# rf_conn.net
KiCad netlist of a schematic drawn in Altium Designer
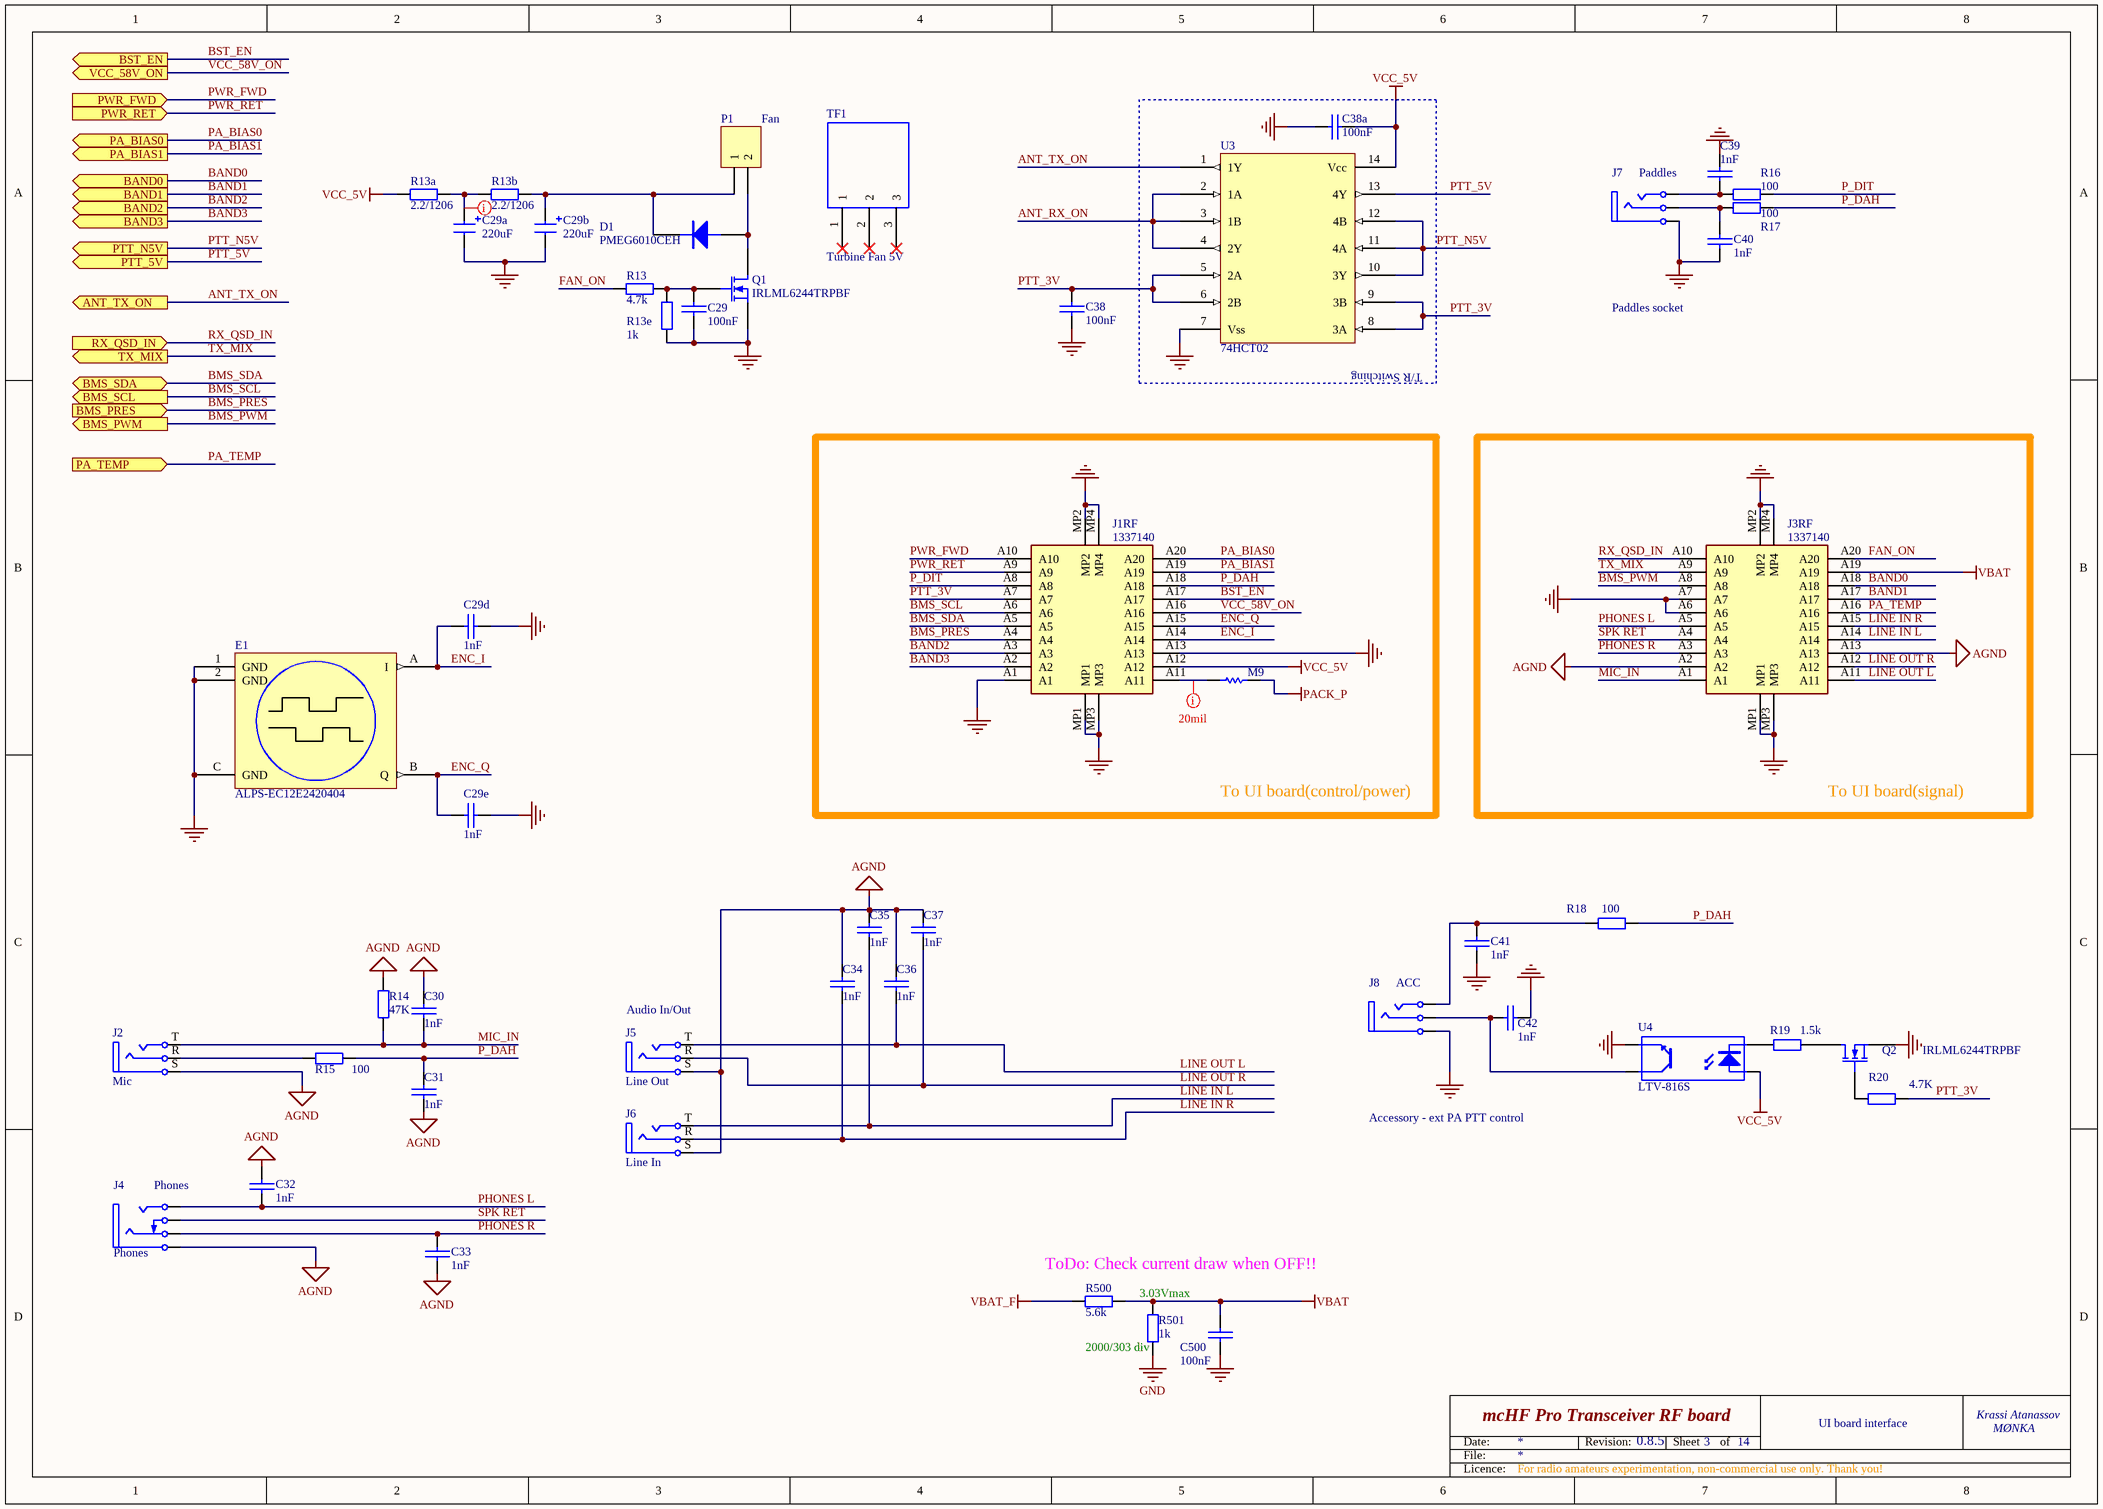
[diagram p0: rf_conn.SchDoc]

(export (version "E")
  (design (tool "Eeschema 10.0.6"))
  (components
    (comp (ref "C29")
      (value "100nF")
      (footprint "0805")
      (description "Capacitor")
      (libsource (lib "mcHF_ui") (part "CAP"))
    )
    (comp (ref "C29a")
      (value "220uF")
      (footprint "CAP_ALUM_Pro")
      (description "Electrolitic capacitor")
      (libsource (lib "mcHF_ui") (part "CAP-POL"))
    )
    (comp (ref "C29b")
      (value "220uF")
      (footprint "CAP_ALUM_Pro")
      (description "Electrolitic capacitor")
      (libsource (lib "mcHF_ui") (part "CAP-POL"))
    )
    (comp (ref "C29d")
      (value "1nF")
      (footprint "0805")
      (description "Capacitor")
      (libsource (lib "mcHF_ui") (part "CAP"))
    )
    (comp (ref "C29e")
      (value "1nF")
      (footprint "0805")
      (description "Capacitor")
      (libsource (lib "mcHF_ui") (part "CAP"))
    )
    (comp (ref "C30")
      (value "1nF")
      (footprint "0805")
      (description "Capacitor")
      (libsource (lib "mcHF_ui") (part "CAP"))
    )
    (comp (ref "C31")
      (value "1nF")
      (footprint "0805")
      (description "Capacitor")
      (libsource (lib "mcHF_ui") (part "CAP"))
    )
    (comp (ref "C32")
      (value "1nF")
      (footprint "0805")
      (description "Capacitor")
      (libsource (lib "mcHF_ui") (part "CAP"))
    )
    (comp (ref "C33")
      (value "1nF")
      (footprint "0805")
      (description "Capacitor")
      (libsource (lib "mcHF_ui") (part "CAP"))
    )
    (comp (ref "C34")
      (value "1nF")
      (footprint "0805")
      (description "Capacitor")
      (libsource (lib "mcHF_ui") (part "CAP"))
    )
    (comp (ref "C35")
      (value "1nF")
      (footprint "0805")
      (description "Capacitor")
      (libsource (lib "mcHF_ui") (part "CAP"))
    )
    (comp (ref "C36")
      (value "1nF")
      (footprint "0805")
      (description "Capacitor")
      (libsource (lib "mcHF_ui") (part "CAP"))
    )
    (comp (ref "C37")
      (value "1nF")
      (footprint "0805")
      (description "Capacitor")
      (libsource (lib "mcHF_ui") (part "CAP"))
    )
    (comp (ref "C38")
      (value "100nF")
      (footprint "0805")
      (description "Capacitor")
      (libsource (lib "mcHF_rf") (part "CAP"))
    )
    (comp (ref "C38a")
      (value "100nF")
      (footprint "0805")
      (description "Capacitor")
      (libsource (lib "mcHF_rf") (part "CAP"))
    )
    (comp (ref "C39")
      (value "1nF")
      (footprint "0805")
      (description "Capacitor")
      (libsource (lib "mcHF_rf") (part "CAP"))
    )
    (comp (ref "C40")
      (value "1nF")
      (footprint "0805")
      (description "Capacitor")
      (libsource (lib "mcHF_rf") (part "CAP"))
    )
    (comp (ref "C41")
      (value "1nF")
      (footprint "0805")
      (description "Capacitor")
      (libsource (lib "mcHF_rf") (part "CAP"))
    )
    (comp (ref "C42")
      (value "1nF")
      (footprint "0805")
      (description "Capacitor")
      (libsource (lib "mcHF_rf") (part "CAP"))
    )
    (comp (ref "C500")
      (value "100nF")
      (footprint "0805")
      (description "Capacitor")
      (libsource (lib "mcHF_rf") (part "CAP"))
    )
    (comp (ref "D1")
      (value "PMEG6010CEH")
      (footprint "SOD87")
      (description "DIODE, SCHOTTKY, 1A, 60V, SOD-123F")
      (libsource (lib "mcHF_rf") (part "PMEG6010CEH"))
    )
    (comp (ref "E1")
      (value "ALPS-EC12E2420404")
      (footprint "Encoder")
      (description "ALPS Rotary Encoder")
      (libsource (lib "__ui") (part "Encoder"))
    )
    (comp (ref "J1RF")
      (value "1337140")
      (footprint "1373866")
      (fields
        (field (name "MOUSER PART NUMBER") "651-1373866")
        (field (name "MANUFACTURER_PART_NUMBER") "1373866")
      )
      (libsource (lib "1373866") (part "1373866"))
    )
    (comp (ref "J2")
      (value "Mic")
      (footprint "MX-387GL_new1")
      (description "Jack Socket,Thru-Hole")
      (libsource (lib "mcHF_ui") (part "MX-387GL"))
    )
    (comp (ref "J3RF")
      (value "1337140")
      (footprint "1373866")
      (fields
        (field (name "MOUSER PART NUMBER") "651-1373866")
        (field (name "MANUFACTURER_PART_NUMBER") "1373866")
      )
      (libsource (lib "1373866") (part "1373866"))
    )
    (comp (ref "J4")
      (value "Phones")
      (footprint "KLBR4")
      (description "Jack Socket 4 pin")
      (fields (field (name "FUNCTION") "Phones"))
      (libsource (lib "mcHF_ui") (part "PhoneJack"))
    )
    (comp (ref "J5")
      (value "Line Out")
      (footprint "MX-387GL_new1")
      (description "Jack Socket,Thru-Hole")
      (libsource (lib "mcHF_ui") (part "MX-387GL"))
    )
    (comp (ref "J6")
      (value "Line In")
      (footprint "MX-387GL_new1")
      (description "Jack Socket,Thru-Hole")
      (libsource (lib "mcHF_ui") (part "MX-387GL"))
    )
    (comp (ref "J7")
      (value "Paddles")
      (footprint "MX-387GL_new1")
      (description "Jack Socket,Thru-Hole")
      (libsource (lib "mcHF_rf") (part "Phonejack3"))
    )
    (comp (ref "J8")
      (value "ACC")
      (footprint "MX-387GL_new1")
      (description "Jack Socket,Thru-Hole")
      (libsource (lib "mcHF_rf") (part "Phonejack3"))
    )
    (comp (ref "M9")
      (value "0")
      (footprint "SB_0603_10")
      (description "Link")
      (fields (field (name "PUBLISHER") "Altium Limited"))
      (libsource (lib "__ui") (part "Link"))
    )
    (comp (ref "P1")
      (value "Fan")
      (footprint "MHDR1X2_m")
      (description "Header, 2-Pin")
      (fields (field (name "PUBLISHER") "Altium Limited"))
      (libsource (lib "Miscellaneous Connectors") (part "MHDR1X2"))
    )
    (comp (ref "Q1")
      (value "IRLML6244TRPBF")
      (footprint "SOT-23-Pro")
      (description "N-Channel MOSFET")
      (libsource (lib "mcHF_ui_b") (part "MOSFET-N"))
    )
    (comp (ref "Q2")
      (value "IRLML6244TRPBF")
      (footprint "SOT-23-Pro")
      (description "N-Channel MOSFET")
      (libsource (lib "mcHF_ui_b") (part "MOSFET-N"))
    )
    (comp (ref "R13")
      (value "4.7k")
      (footprint "0805")
      (description "Resistor")
      (libsource (lib "") (part "RES_3"))
    )
    (comp (ref "R13a")
      (value "2.2/1206")
      (footprint "1206")
      (description "Resistor")
      (libsource (lib "") (part "RES_2"))
    )
    (comp (ref "R13b")
      (value "2.2/1206")
      (footprint "1206")
      (description "Resistor")
      (libsource (lib "") (part "RES_2"))
    )
    (comp (ref "R13e")
      (value "1k")
      (footprint "0805")
      (description "Resistor")
      (libsource (lib "") (part "RES_1"))
    )
    (comp (ref "R14")
      (value "47K")
      (footprint "0805")
      (description "Resistor")
      (libsource (lib "mcHF_ui") (part "RES"))
    )
    (comp (ref "R15")
      (value "100")
      (footprint "0805")
      (description "Resistor")
      (libsource (lib "") (part "RES_2"))
    )
    (comp (ref "R16")
      (value "100")
      (footprint "0805")
      (description "Resistor")
      (libsource (lib "*") (part "RES"))
    )
    (comp (ref "R17")
      (value "100")
      (footprint "0805")
      (description "Resistor")
      (libsource (lib "*") (part "RES"))
    )
    (comp (ref "R18")
      (value "100")
      (footprint "0805")
      (description "Resistor")
      (libsource (lib "*") (part "RES"))
    )
    (comp (ref "R19")
      (value "1.5k")
      (footprint "0805")
      (description "Resistor")
      (libsource (lib "mcHF_rf") (part "RES"))
    )
    (comp (ref "R20")
      (value "4.7K")
      (footprint "0805")
      (description "Resistor")
      (libsource (lib "mcHF_rf") (part "RES"))
    )
    (comp (ref "R500")
      (value "5.6k")
      (footprint "0805")
      (description "Resistor")
      (libsource (lib "mcHF_rf") (part "RES"))
    )
    (comp (ref "R501")
      (value "1k")
      (footprint "0805")
      (description "Resistor")
      (libsource (lib "") (part "RES_1"))
    )
    (comp (ref "TF1")
      (value "Turbine Fan 5V")
      (footprint "TFAN")
      (description "5V Turbine Fan, 40x40mm")
      (libsource (lib "__rf") (part "FAN5V"))
    )
    (comp (ref "U3")
      (value "74HCT02")
      (footprint "SO-14")
      (description "Quad 2-input NOR gate")
      (libsource (lib "mcHF_rf") (part "74HCT02"))
    )
    (comp (ref "U4")
      (value "LTV-816S")
      (footprint "SMDIP-4_new1")
      (description "OPTOCOUPLER, SMDIP-4, TR O/P")
      (libsource (lib "mcHF_rf") (part "ISP817XSM"))
    )
  )
  (nets
    (net (code "1") (name "/ANT_RX_ON") (class "Default")
      (node (ref "U3") (pin "2") (pinfunction "1A_2") (pintype "input"))
      (node (ref "U3") (pin "3") (pinfunction "1B_3") (pintype "input"))
      (node (ref "U3") (pin "4") (pinfunction "2Y_4") (pintype "output"))
    )
    (net (code "2") (name "/ANT_TX_ON") (class "Default")
      (node (ref "U3") (pin "1") (pinfunction "1Y_1") (pintype "output"))
    )
    (net (code "3") (name "/BAND0") (class "Default")
      (node (ref "J3RF") (pin "A18") (pinfunction "A18_A18") (pintype "passive"))
    )
    (net (code "4") (name "/BAND1") (class "Default")
      (node (ref "J3RF") (pin "A17") (pinfunction "A17_A17") (pintype "passive"))
    )
    (net (code "5") (name "/BAND2") (class "Default")
      (node (ref "J1RF") (pin "A3") (pinfunction "A3_A3") (pintype "passive"))
    )
    (net (code "6") (name "/BAND3") (class "Default")
      (node (ref "J1RF") (pin "A2") (pinfunction "A2_A2") (pintype "passive"))
    )
    (net (code "7") (name "/BMS_PRES") (class "Default")
      (node (ref "J1RF") (pin "A4") (pinfunction "A4_A4") (pintype "passive"))
    )
    (net (code "8") (name "/BMS_PWM") (class "Default")
      (node (ref "J3RF") (pin "A8") (pinfunction "A8_A8") (pintype "passive"))
    )
    (net (code "9") (name "/BMS_SCL") (class "Default")
      (node (ref "J1RF") (pin "A6") (pinfunction "A6_A6") (pintype "passive"))
    )
    (net (code "10") (name "/BMS_SDA") (class "Default")
      (node (ref "J1RF") (pin "A5") (pinfunction "A5_A5") (pintype "passive"))
    )
    (net (code "11") (name "/BST_EN") (class "Default")
      (node (ref "J1RF") (pin "A17") (pinfunction "A17_A17") (pintype "passive"))
    )
    (net (code "12") (name "/ENC_I") (class "Default")
      (node (ref "C29d") (pin "1") (pinfunction "1_1") (pintype "passive"))
      (node (ref "E1") (pin "A") (pinfunction "I_A") (pintype "output"))
      (node (ref "J1RF") (pin "A14") (pinfunction "A14_A14") (pintype "passive"))
    )
    (net (code "13") (name "/ENC_Q") (class "Default")
      (node (ref "C29e") (pin "1") (pinfunction "1_1") (pintype "passive"))
      (node (ref "E1") (pin "B") (pinfunction "Q_B") (pintype "output"))
      (node (ref "J1RF") (pin "A15") (pinfunction "A15_A15") (pintype "passive"))
    )
    (net (code "14") (name "/FAN_ON") (class "Default")
      (node (ref "J3RF") (pin "A20") (pinfunction "A20_A20") (pintype "passive"))
      (node (ref "R13") (pin "2") (pinfunction "2_2") (pintype "passive"))
    )
    (net (code "15") (name "/LINE IN L") (class "Default")
      (node (ref "C35") (pin "2") (pinfunction "2_2") (pintype "passive"))
      (node (ref "J3RF") (pin "A14") (pinfunction "A14_A14") (pintype "passive"))
      (node (ref "J6") (pin "T") (pinfunction "1_T") (pintype "passive"))
    )
    (net (code "16") (name "/LINE IN R") (class "Default")
      (node (ref "C34") (pin "2") (pinfunction "2_2") (pintype "passive"))
      (node (ref "J3RF") (pin "A15") (pinfunction "A15_A15") (pintype "passive"))
      (node (ref "J6") (pin "R") (pinfunction "3_R") (pintype "passive"))
    )
    (net (code "17") (name "/LINE OUT L") (class "Default")
      (node (ref "C36") (pin "2") (pinfunction "2_2") (pintype "passive"))
      (node (ref "J3RF") (pin "A11") (pinfunction "A11_A11") (pintype "passive"))
      (node (ref "J5") (pin "T") (pinfunction "1_T") (pintype "passive"))
    )
    (net (code "18") (name "/LINE OUT R") (class "Default")
      (node (ref "C37") (pin "2") (pinfunction "2_2") (pintype "passive"))
      (node (ref "J3RF") (pin "A12") (pinfunction "A12_A12") (pintype "passive"))
      (node (ref "J5") (pin "R") (pinfunction "3_R") (pintype "passive"))
    )
    (net (code "19") (name "/MIC_IN") (class "Default")
      (node (ref "C30") (pin "2") (pinfunction "2_2") (pintype "passive"))
      (node (ref "J2") (pin "T") (pinfunction "1_T") (pintype "passive"))
      (node (ref "J3RF") (pin "A1") (pinfunction "A1_A1") (pintype "passive"))
      (node (ref "R14") (pin "1") (pinfunction "1_1") (pintype "passive"))
    )
    (net (code "20") (name "/PA_BIAS0") (class "Default")
      (node (ref "J1RF") (pin "A20") (pinfunction "A20_A20") (pintype "passive"))
    )
    (net (code "21") (name "/PA_BIAS1") (class "Default")
      (node (ref "J1RF") (pin "A19") (pinfunction "A19_A19") (pintype "passive"))
    )
    (net (code "22") (name "/PA_TEMP") (class "Default")
      (node (ref "J3RF") (pin "A16") (pinfunction "A16_A16") (pintype "passive"))
    )
    (net (code "23") (name "/PHONES L") (class "Default")
      (node (ref "C32") (pin "1") (pinfunction "1_1") (pintype "passive"))
      (node (ref "J3RF") (pin "A5") (pinfunction "A5_A5") (pintype "passive"))
      (node (ref "J4") (pin "T") (pinfunction "T_T") (pintype "passive"))
    )
    (net (code "24") (name "/PHONES R") (class "Default")
      (node (ref "C33") (pin "2") (pinfunction "2_2") (pintype "passive"))
      (node (ref "J3RF") (pin "A3") (pinfunction "A3_A3") (pintype "passive"))
      (node (ref "J4") (pin "R") (pinfunction "R_R") (pintype "passive"))
    )
    (net (code "25") (name "/PTT_3V") (class "Default")
      (node (ref "C38") (pin "1") (pinfunction "1_1") (pintype "passive"))
      (node (ref "J1RF") (pin "A7") (pinfunction "A7_A7") (pintype "passive"))
      (node (ref "R20") (pin "2") (pinfunction "2_2") (pintype "passive"))
      (node (ref "U3") (pin "5") (pinfunction "2A_5") (pintype "input"))
      (node (ref "U3") (pin "6") (pinfunction "2B_6") (pintype "input"))
      (node (ref "U3") (pin "8") (pinfunction "3A_8") (pintype "input"))
      (node (ref "U3") (pin "9") (pinfunction "3B_9") (pintype "input"))
    )
    (net (code "26") (name "/PTT_5V") (class "Default")
      (node (ref "U3") (pin "13") (pinfunction "4Y_13") (pintype "output"))
    )
    (net (code "27") (name "/PTT_N5V") (class "Default")
      (node (ref "U3") (pin "10") (pinfunction "3Y_10") (pintype "output"))
      (node (ref "U3") (pin "11") (pinfunction "4A_11") (pintype "input"))
      (node (ref "U3") (pin "12") (pinfunction "4B_12") (pintype "input"))
    )
    (net (code "28") (name "/PWR_FWD") (class "Default")
      (node (ref "J1RF") (pin "A10") (pinfunction "A10_A10") (pintype "passive"))
    )
    (net (code "29") (name "/PWR_RET") (class "Default")
      (node (ref "J1RF") (pin "A9") (pinfunction "A9_A9") (pintype "passive"))
    )
    (net (code "30") (name "/P_DAH") (class "Default")
      (node (ref "C31") (pin "1") (pinfunction "1_1") (pintype "passive"))
      (node (ref "J1RF") (pin "A18") (pinfunction "A18_A18") (pintype "passive"))
      (node (ref "R15") (pin "2") (pinfunction "2_2") (pintype "passive"))
      (node (ref "R17") (pin "1") (pinfunction "1_1") (pintype "passive"))
      (node (ref "R18") (pin "1") (pinfunction "1_1") (pintype "passive"))
    )
    (net (code "31") (name "/P_DIT") (class "Default")
      (node (ref "J1RF") (pin "A8") (pinfunction "A8_A8") (pintype "passive"))
      (node (ref "R16") (pin "1") (pinfunction "1_1") (pintype "passive"))
    )
    (net (code "32") (name "/RX_QSD_IN") (class "Default")
      (node (ref "J3RF") (pin "A10") (pinfunction "A10_A10") (pintype "passive"))
    )
    (net (code "33") (name "/SPK RET") (class "Default")
      (node (ref "J3RF") (pin "A4") (pinfunction "A4_A4") (pintype "passive"))
      (node (ref "J4") (pin "B") (pinfunction "B_B") (pintype "passive"))
    )
    (net (code "34") (name "/TX_MIX") (class "Default")
      (node (ref "J3RF") (pin "A9") (pinfunction "A9_A9") (pintype "passive"))
    )
    (net (code "35") (name "/VCC_58V_ON") (class "Default")
      (node (ref "J1RF") (pin "A16") (pinfunction "A16_A16") (pintype "passive"))
    )
    (net (code "36") (name "AGND") (class "Default")
      (node (ref "C30") (pin "1") (pinfunction "1_1") (pintype "passive"))
      (node (ref "C31") (pin "2") (pinfunction "2_2") (pintype "passive"))
      (node (ref "C32") (pin "2") (pinfunction "2_2") (pintype "passive"))
      (node (ref "C33") (pin "1") (pinfunction "1_1") (pintype "passive"))
      (node (ref "C34") (pin "1") (pinfunction "1_1") (pintype "passive"))
      (node (ref "C35") (pin "1") (pinfunction "1_1") (pintype "passive"))
      (node (ref "C36") (pin "1") (pinfunction "1_1") (pintype "passive"))
      (node (ref "C37") (pin "1") (pinfunction "1_1") (pintype "passive"))
      (node (ref "J2") (pin "S") (pinfunction "2_S") (pintype "power_in"))
      (node (ref "J3RF") (pin "A13") (pinfunction "A13_A13") (pintype "passive"))
      (node (ref "J3RF") (pin "A2") (pinfunction "A2_A2") (pintype "passive"))
      (node (ref "J4") (pin "S") (pinfunction "S_S") (pintype "power_in"))
      (node (ref "J5") (pin "S") (pinfunction "2_S") (pintype "power_in"))
      (node (ref "J6") (pin "S") (pinfunction "2_S") (pintype "power_in"))
      (node (ref "R14") (pin "2") (pinfunction "2_2") (pintype "passive"))
    )
    (net (code "37") (name "GND") (class "Default")
      (node (ref "C29") (pin "2") (pinfunction "2_2") (pintype "passive"))
      (node (ref "C29a") (pin "2") (pinfunction "2_2") (pintype "passive"))
      (node (ref "C29b") (pin "2") (pinfunction "2_2") (pintype "passive"))
      (node (ref "C29d") (pin "2") (pinfunction "2_2") (pintype "passive"))
      (node (ref "C29e") (pin "2") (pinfunction "2_2") (pintype "passive"))
      (node (ref "C38") (pin "2") (pinfunction "2_2") (pintype "passive"))
      (node (ref "C38a") (pin "2") (pinfunction "2_2") (pintype "passive"))
      (node (ref "C39") (pin "2") (pinfunction "2_2") (pintype "passive"))
      (node (ref "C40") (pin "1") (pinfunction "1_1") (pintype "passive"))
      (node (ref "C41") (pin "2") (pinfunction "2_2") (pintype "passive"))
      (node (ref "C42") (pin "1") (pinfunction "1_1") (pintype "passive"))
      (node (ref "C500") (pin "2") (pinfunction "2_2") (pintype "passive"))
      (node (ref "E1") (pin "1") (pinfunction "GND_1") (pintype "power_in"))
      (node (ref "E1") (pin "2") (pinfunction "GND_2") (pintype "power_in"))
      (node (ref "E1") (pin "C") (pinfunction "GND_C") (pintype "power_in"))
      (node (ref "J1RF") (pin "A1") (pinfunction "A1_A1") (pintype "passive"))
      (node (ref "J1RF") (pin "A13") (pinfunction "A13_A13") (pintype "passive"))
      (node (ref "J1RF") (pin "MP1") (pinfunction "MP1_MP1") (pintype "passive"))
      (node (ref "J1RF") (pin "MP2") (pinfunction "MP2_MP2") (pintype "passive"))
      (node (ref "J1RF") (pin "MP3") (pinfunction "MP3_MP3") (pintype "passive"))
      (node (ref "J1RF") (pin "MP4") (pinfunction "MP4_MP4") (pintype "passive"))
      (node (ref "J3RF") (pin "A6") (pinfunction "A6_A6") (pintype "passive"))
      (node (ref "J3RF") (pin "A7") (pinfunction "A7_A7") (pintype "passive"))
      (node (ref "J3RF") (pin "MP1") (pinfunction "MP1_MP1") (pintype "passive"))
      (node (ref "J3RF") (pin "MP2") (pinfunction "MP2_MP2") (pintype "passive"))
      (node (ref "J3RF") (pin "MP3") (pinfunction "MP3_MP3") (pintype "passive"))
      (node (ref "J3RF") (pin "MP4") (pinfunction "MP4_MP4") (pintype "passive"))
      (node (ref "J7") (pin "S") (pinfunction "S_S") (pintype "power_in"))
      (node (ref "J8") (pin "S") (pinfunction "S_S") (pintype "power_in"))
      (node (ref "Q1") (pin "2") (pinfunction "S_2") (pintype "passive"))
      (node (ref "Q2") (pin "2") (pinfunction "S_2") (pintype "passive"))
      (node (ref "R13e") (pin "2") (pinfunction "2_2") (pintype "passive"))
      (node (ref "R501") (pin "2") (pinfunction "2_2") (pintype "passive"))
      (node (ref "U3") (pin "7") (pinfunction "Vss_7") (pintype "power_in"))
      (node (ref "U4") (pin "3") (pinfunction "E_3") (pintype "passive"))
    )
    (net (code "38") (name "Net-(C29a-Pad1)") (class "Default")
      (node (ref "C29a") (pin "1") (pinfunction "1_1") (pintype "passive"))
      (node (ref "R13a") (pin "2") (pinfunction "2_2") (pintype "passive"))
      (node (ref "R13b") (pin "1") (pinfunction "1_1") (pintype "passive"))
    )
    (net (code "39") (name "Net-(C39-Pad1)") (class "Default")
      (node (ref "C39") (pin "1") (pinfunction "1_1") (pintype "passive"))
      (node (ref "J7") (pin "T") (pinfunction "T_T") (pintype "passive"))
      (node (ref "R16") (pin "2") (pinfunction "2_2") (pintype "passive"))
    )
    (net (code "40") (name "Net-(C40-Pad2)") (class "Default")
      (node (ref "C40") (pin "2") (pinfunction "2_2") (pintype "passive"))
      (node (ref "J7") (pin "R") (pinfunction "R_R") (pintype "passive"))
      (node (ref "R17") (pin "2") (pinfunction "2_2") (pintype "passive"))
    )
    (net (code "41") (name "Net-(C41-Pad1)") (class "Default")
      (node (ref "C41") (pin "1") (pinfunction "1_1") (pintype "passive"))
      (node (ref "J8") (pin "T") (pinfunction "T_T") (pintype "passive"))
      (node (ref "R18") (pin "2") (pinfunction "2_2") (pintype "passive"))
    )
    (net (code "42") (name "Net-(D1-A)") (class "Default")
      (node (ref "D1") (pin "1") (pinfunction "A_1") (pintype "passive"))
      (node (ref "P1") (pin "2") (pinfunction "2_2") (pintype "passive"))
      (node (ref "Q1") (pin "3") (pinfunction "D_3") (pintype "passive"))
    )
    (net (code "43") (name "Net-(D1-K)") (class "Default")
      (node (ref "C29b") (pin "1") (pinfunction "1_1") (pintype "passive"))
      (node (ref "D1") (pin "2") (pinfunction "K_2") (pintype "passive"))
      (node (ref "P1") (pin "1") (pinfunction "1_1") (pintype "passive"))
      (node (ref "R13b") (pin "2") (pinfunction "2_2") (pintype "passive"))
    )
    (net (code "44") (name "Net-(J1RF-PadA11)") (class "Default")
      (node (ref "J1RF") (pin "A11") (pinfunction "A11_A11") (pintype "passive"))
      (node (ref "M9") (pin "1") (pinfunction "1_1") (pintype "passive"))
    )
    (net (code "45") (name "Net-(J2-3)") (class "Default")
      (node (ref "J2") (pin "R") (pinfunction "3_R") (pintype "passive"))
      (node (ref "R15") (pin "1") (pinfunction "1_1") (pintype "passive"))
    )
    (net (code "46") (name "Net-(Q1-G)") (class "Default")
      (node (ref "C29") (pin "1") (pinfunction "1_1") (pintype "passive"))
      (node (ref "Q1") (pin "1") (pinfunction "G_1") (pintype "passive"))
      (node (ref "R13") (pin "1") (pinfunction "1_1") (pintype "passive"))
      (node (ref "R13e") (pin "1") (pinfunction "1_1") (pintype "passive"))
    )
    (net (code "47") (name "Net-(Q2-D)") (class "Default")
      (node (ref "Q2") (pin "3") (pinfunction "D_3") (pintype "passive"))
      (node (ref "R19") (pin "2") (pinfunction "2_2") (pintype "passive"))
    )
    (net (code "48") (name "Net-(Q2-G)") (class "Default")
      (node (ref "Q2") (pin "1") (pinfunction "G_1") (pintype "passive"))
      (node (ref "R20") (pin "1") (pinfunction "1_1") (pintype "passive"))
    )
    (net (code "49") (name "Net-(U4-C)") (class "Default")
      (node (ref "C42") (pin "2") (pinfunction "2_2") (pintype "passive"))
      (node (ref "J8") (pin "R") (pinfunction "R_R") (pintype "passive"))
      (node (ref "U4") (pin "4") (pinfunction "C_4") (pintype "passive"))
    )
    (net (code "50") (name "Net-(U4-K)") (class "Default")
      (node (ref "R19") (pin "1") (pinfunction "1_1") (pintype "passive"))
      (node (ref "U4") (pin "2") (pinfunction "K_2") (pintype "passive"))
    )
    (net (code "51") (name "PACK_P") (class "Default")
      (node (ref "M9") (pin "2") (pinfunction "2_2") (pintype "passive"))
    )
    (net (code "52") (name "VBAT") (class "Default")
      (node (ref "C500") (pin "1") (pinfunction "1_1") (pintype "passive"))
      (node (ref "J3RF") (pin "A19") (pinfunction "A19_A19") (pintype "passive"))
      (node (ref "R500") (pin "2") (pinfunction "2_2") (pintype "passive"))
      (node (ref "R501") (pin "1") (pinfunction "1_1") (pintype "passive"))
    )
    (net (code "53") (name "VBAT_F") (class "Default")
      (node (ref "R500") (pin "1") (pinfunction "1_1") (pintype "passive"))
    )
    (net (code "54") (name "VCC_5V") (class "Default")
      (node (ref "C38a") (pin "1") (pinfunction "1_1") (pintype "passive"))
      (node (ref "J1RF") (pin "A12") (pinfunction "A12_A12") (pintype "passive"))
      (node (ref "R13a") (pin "1") (pinfunction "1_1") (pintype "passive"))
      (node (ref "U3") (pin "14") (pinfunction "Vcc_14") (pintype "power_in"))
      (node (ref "U4") (pin "1") (pinfunction "A_1") (pintype "passive"))
    )
    (net (code "55") (name "unconnected-(TF1-Pad1)") (class "Default")
      (node (ref "TF1") (pin "1") (pinfunction "1_1") (pintype "passive+no_connect"))
    )
    (net (code "56") (name "unconnected-(TF1-Pad2)") (class "Default")
      (node (ref "TF1") (pin "2") (pinfunction "2_2") (pintype "passive+no_connect"))
    )
    (net (code "57") (name "unconnected-(TF1-Pad3)") (class "Default")
      (node (ref "TF1") (pin "3") (pinfunction "3_3") (pintype "passive+no_connect"))
    )
  )
)
